# 2022.net
KiCad netlist of a schematic drawn in EAGLE
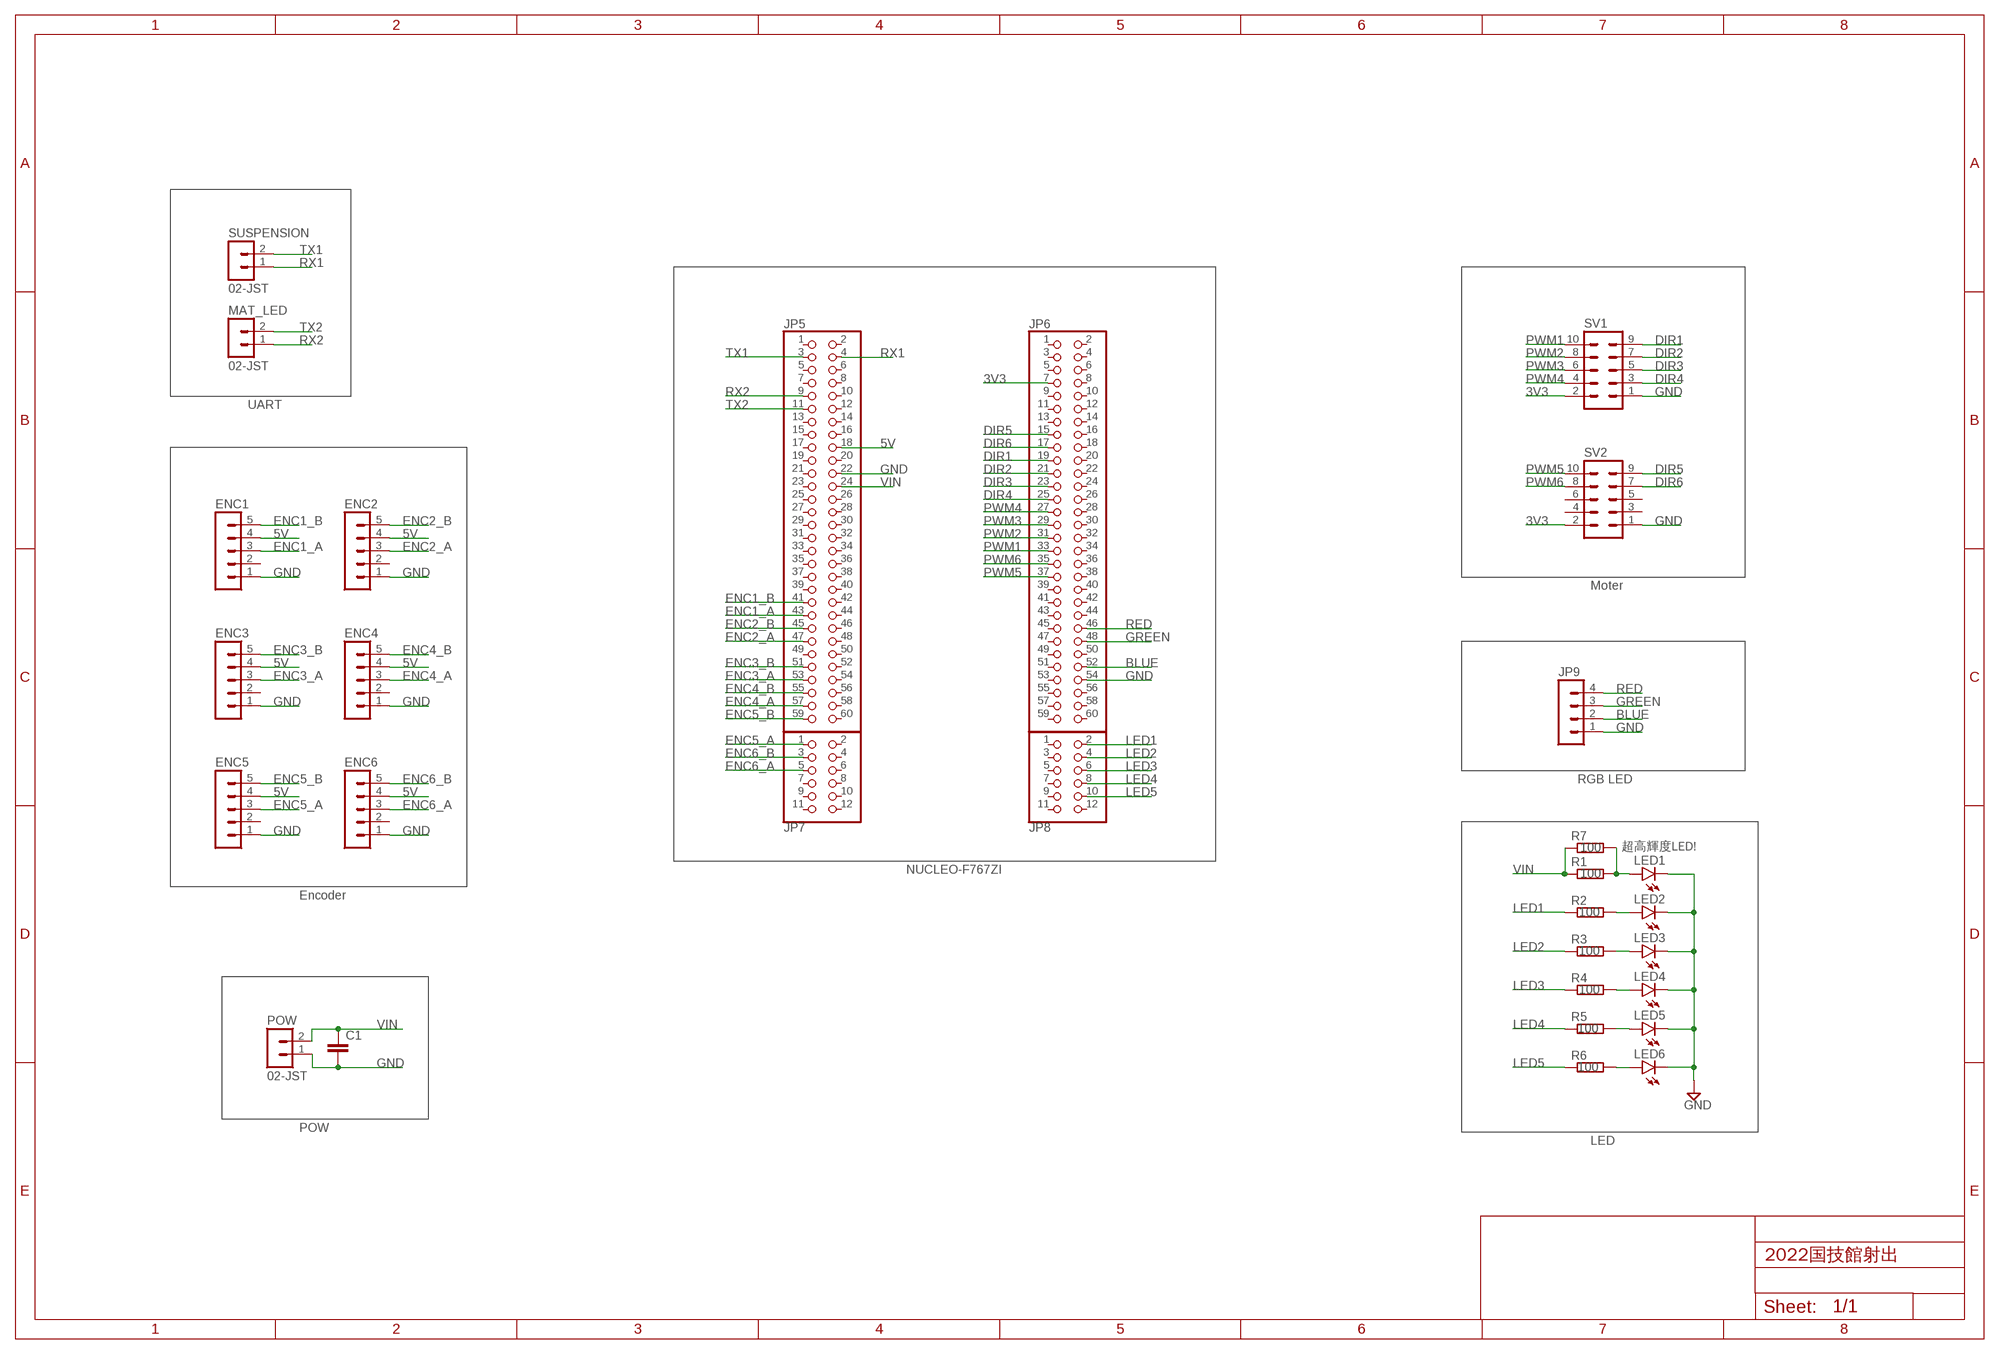
[diagram p0: schematic, sheet 1]

(export (version "E")
  (design (tool "Eeschema 10.0.6"))
  (components
    (comp (ref "C1")
      (value "C-EU025-024X044")
      (footprint "eagle-import:C025-024X044")
      (libsource (lib "eagle-import") (part "C-EU025-024X044"))
    )
    (comp (ref "ENC1")
      (value "05-JST")
      (footprint "eagle-import:B5B-XH")
      (libsource (lib "eagle-import") (part "05-JST"))
    )
    (comp (ref "ENC2")
      (value "05-JST")
      (footprint "eagle-import:B5B-XH")
      (libsource (lib "eagle-import") (part "05-JST"))
    )
    (comp (ref "ENC3")
      (value "05-JST")
      (footprint "eagle-import:B5B-XH")
      (libsource (lib "eagle-import") (part "05-JST"))
    )
    (comp (ref "ENC4")
      (value "05-JST")
      (footprint "eagle-import:B5B-XH")
      (libsource (lib "eagle-import") (part "05-JST"))
    )
    (comp (ref "ENC5")
      (value "05-JST")
      (footprint "eagle-import:B5B-XH")
      (libsource (lib "eagle-import") (part "05-JST"))
    )
    (comp (ref "ENC6")
      (value "05-JST")
      (footprint "eagle-import:B5B-XH")
      (libsource (lib "eagle-import") (part "05-JST"))
    )
    (comp (ref "JP5")
      (value "PINHD-2X30")
      (footprint "eagle-import:2X30")
      (libsource (lib "eagle-import") (part "PINHD-2X30"))
    )
    (comp (ref "JP6")
      (value "PINHD-2X30")
      (footprint "eagle-import:2X30")
      (libsource (lib "eagle-import") (part "PINHD-2X30"))
    )
    (comp (ref "JP7")
      (value "PINHD-2X6")
      (footprint "eagle-import:2X06")
      (libsource (lib "eagle-import") (part "PINHD-2X6"))
    )
    (comp (ref "JP8")
      (value "PINHD-2X6")
      (footprint "eagle-import:2X06")
      (libsource (lib "eagle-import") (part "PINHD-2X6"))
    )
    (comp (ref "JP9")
      (value "04-JST")
      (footprint "eagle-import:B4B-XH")
      (libsource (lib "eagle-import") (part "04-JST"))
    )
    (comp (ref "LED1")
      (value "LED5MM")
      (footprint "eagle-import:LED5MM")
      (libsource (lib "eagle-import") (part "LED5MM"))
    )
    (comp (ref "LED2")
      (value "LED5MM")
      (footprint "eagle-import:LED5MM")
      (libsource (lib "eagle-import") (part "LED5MM"))
    )
    (comp (ref "LED3")
      (value "LED5MM")
      (footprint "eagle-import:LED5MM")
      (libsource (lib "eagle-import") (part "LED5MM"))
    )
    (comp (ref "LED4")
      (value "LED5MM")
      (footprint "eagle-import:LED5MM")
      (libsource (lib "eagle-import") (part "LED5MM"))
    )
    (comp (ref "LED5")
      (value "LED5MM")
      (footprint "eagle-import:LED5MM")
      (libsource (lib "eagle-import") (part "LED5MM"))
    )
    (comp (ref "LED6")
      (value "LED5MM")
      (footprint "eagle-import:LED5MM")
      (libsource (lib "eagle-import") (part "LED5MM"))
    )
    (comp (ref "MAT_LED")
      (value "02-JST")
      (footprint "eagle-import:B2B-XH")
      (libsource (lib "eagle-import") (part "02-JST"))
    )
    (comp (ref "POW")
      (value "02-JST")
      (footprint "eagle-import:B2B-XH")
      (libsource (lib "eagle-import") (part "02-JST"))
    )
    (comp (ref "R1")
      (value "100")
      (footprint "eagle-import:0204_7")
      (libsource (lib "eagle-import") (part "R-EU_0204/7"))
    )
    (comp (ref "R2")
      (value "100")
      (footprint "eagle-import:0204_7")
      (libsource (lib "eagle-import") (part "R-EU_0204/7"))
    )
    (comp (ref "R3")
      (value "100")
      (footprint "eagle-import:0204_7")
      (libsource (lib "eagle-import") (part "R-EU_0204/7"))
    )
    (comp (ref "R4")
      (value "100")
      (footprint "eagle-import:0204_7")
      (libsource (lib "eagle-import") (part "R-EU_0204/7"))
    )
    (comp (ref "R5")
      (value "100")
      (footprint "eagle-import:0204_7")
      (libsource (lib "eagle-import") (part "R-EU_0204/7"))
    )
    (comp (ref "R6")
      (value "100")
      (footprint "eagle-import:0204_7")
      (libsource (lib "eagle-import") (part "R-EU_0204/7"))
    )
    (comp (ref "R7")
      (value "100")
      (footprint "eagle-import:0204_7")
      (libsource (lib "eagle-import") (part "R-EU_0204/7"))
    )
    (comp (ref "SUSPENSION")
      (value "02-JST")
      (footprint "eagle-import:B2B-XH")
      (libsource (lib "eagle-import") (part "02-JST"))
    )
    (comp (ref "SV1")
      (value "ML10")
      (footprint "eagle-import:ML10")
      (libsource (lib "eagle-import") (part "ML10"))
    )
    (comp (ref "SV2")
      (value "ML10")
      (footprint "eagle-import:ML10")
      (libsource (lib "eagle-import") (part "ML10"))
    )
  )
  (nets
    (net (code "1") (name "/3V3") (class "Default")
      (node (ref "JP6") (pin "7") (pinfunction "7_7") (pintype "passive"))
      (node (ref "SV1") (pin "2") (pinfunction "2_2") (pintype "passive"))
      (node (ref "SV2") (pin "2") (pinfunction "2_2") (pintype "passive"))
    )
    (net (code "2") (name "/5V") (class "Default")
      (node (ref "ENC1") (pin "4") (pinfunction "4_4") (pintype "passive"))
      (node (ref "ENC2") (pin "4") (pinfunction "4_4") (pintype "passive"))
      (node (ref "ENC3") (pin "4") (pinfunction "4_4") (pintype "passive"))
      (node (ref "ENC4") (pin "4") (pinfunction "4_4") (pintype "passive"))
      (node (ref "ENC5") (pin "4") (pinfunction "4_4") (pintype "passive"))
      (node (ref "ENC6") (pin "4") (pinfunction "4_4") (pintype "passive"))
      (node (ref "JP5") (pin "18") (pinfunction "18_18") (pintype "passive"))
    )
    (net (code "3") (name "/BLUE") (class "Default")
      (node (ref "JP6") (pin "52") (pinfunction "52_52") (pintype "passive"))
      (node (ref "JP9") (pin "2") (pinfunction "2_2") (pintype "passive"))
    )
    (net (code "4") (name "/DIR1") (class "Default")
      (node (ref "JP6") (pin "19") (pinfunction "19_19") (pintype "passive"))
      (node (ref "SV1") (pin "9") (pinfunction "9_9") (pintype "passive"))
    )
    (net (code "5") (name "/DIR2") (class "Default")
      (node (ref "JP6") (pin "21") (pinfunction "21_21") (pintype "passive"))
      (node (ref "SV1") (pin "7") (pinfunction "7_7") (pintype "passive"))
    )
    (net (code "6") (name "/DIR3") (class "Default")
      (node (ref "JP6") (pin "23") (pinfunction "23_23") (pintype "passive"))
      (node (ref "SV1") (pin "5") (pinfunction "5_5") (pintype "passive"))
    )
    (net (code "7") (name "/DIR4") (class "Default")
      (node (ref "JP6") (pin "25") (pinfunction "25_25") (pintype "passive"))
      (node (ref "SV1") (pin "3") (pinfunction "3_3") (pintype "passive"))
    )
    (net (code "8") (name "/DIR5") (class "Default")
      (node (ref "JP6") (pin "15") (pinfunction "15_15") (pintype "passive"))
      (node (ref "SV2") (pin "9") (pinfunction "9_9") (pintype "passive"))
    )
    (net (code "9") (name "/DIR6") (class "Default")
      (node (ref "JP6") (pin "17") (pinfunction "17_17") (pintype "passive"))
      (node (ref "SV2") (pin "7") (pinfunction "7_7") (pintype "passive"))
    )
    (net (code "10") (name "/ENC1_A") (class "Default")
      (node (ref "ENC1") (pin "3") (pinfunction "3_3") (pintype "passive"))
      (node (ref "JP5") (pin "43") (pinfunction "43_43") (pintype "passive"))
    )
    (net (code "11") (name "/ENC1_B") (class "Default")
      (node (ref "ENC1") (pin "5") (pinfunction "5_5") (pintype "passive"))
      (node (ref "JP5") (pin "41") (pinfunction "41_41") (pintype "passive"))
    )
    (net (code "12") (name "/ENC2_A") (class "Default")
      (node (ref "ENC2") (pin "3") (pinfunction "3_3") (pintype "passive"))
      (node (ref "JP5") (pin "47") (pinfunction "47_47") (pintype "passive"))
    )
    (net (code "13") (name "/ENC2_B") (class "Default")
      (node (ref "ENC2") (pin "5") (pinfunction "5_5") (pintype "passive"))
      (node (ref "JP5") (pin "45") (pinfunction "45_45") (pintype "passive"))
    )
    (net (code "14") (name "/ENC3_A") (class "Default")
      (node (ref "ENC3") (pin "3") (pinfunction "3_3") (pintype "passive"))
      (node (ref "JP5") (pin "53") (pinfunction "53_53") (pintype "passive"))
    )
    (net (code "15") (name "/ENC3_B") (class "Default")
      (node (ref "ENC3") (pin "5") (pinfunction "5_5") (pintype "passive"))
      (node (ref "JP5") (pin "51") (pinfunction "51_51") (pintype "passive"))
    )
    (net (code "16") (name "/ENC4_A") (class "Default")
      (node (ref "ENC4") (pin "3") (pinfunction "3_3") (pintype "passive"))
      (node (ref "JP5") (pin "57") (pinfunction "57_57") (pintype "passive"))
    )
    (net (code "17") (name "/ENC4_B") (class "Default")
      (node (ref "ENC4") (pin "5") (pinfunction "5_5") (pintype "passive"))
      (node (ref "JP5") (pin "55") (pinfunction "55_55") (pintype "passive"))
    )
    (net (code "18") (name "/ENC5_A") (class "Default")
      (node (ref "ENC5") (pin "3") (pinfunction "3_3") (pintype "passive"))
      (node (ref "JP7") (pin "1") (pinfunction "1_1") (pintype "passive"))
    )
    (net (code "19") (name "/ENC5_B") (class "Default")
      (node (ref "ENC5") (pin "5") (pinfunction "5_5") (pintype "passive"))
      (node (ref "JP5") (pin "59") (pinfunction "59_59") (pintype "passive"))
    )
    (net (code "20") (name "/ENC6_A") (class "Default")
      (node (ref "ENC6") (pin "3") (pinfunction "3_3") (pintype "passive"))
      (node (ref "JP7") (pin "5") (pinfunction "5_5") (pintype "passive"))
    )
    (net (code "21") (name "/ENC6_B") (class "Default")
      (node (ref "ENC6") (pin "5") (pinfunction "5_5") (pintype "passive"))
      (node (ref "JP7") (pin "3") (pinfunction "3_3") (pintype "passive"))
    )
    (net (code "22") (name "/GREEN") (class "Default")
      (node (ref "JP6") (pin "48") (pinfunction "48_48") (pintype "passive"))
      (node (ref "JP9") (pin "3") (pinfunction "3_3") (pintype "passive"))
    )
    (net (code "23") (name "/LED1") (class "Default")
      (node (ref "JP8") (pin "2") (pinfunction "2_2") (pintype "passive"))
      (node (ref "R2") (pin "1") (pinfunction "1_1") (pintype "passive"))
    )
    (net (code "24") (name "/LED2") (class "Default")
      (node (ref "JP8") (pin "4") (pinfunction "4_4") (pintype "passive"))
      (node (ref "R3") (pin "1") (pinfunction "1_1") (pintype "passive"))
    )
    (net (code "25") (name "/LED3") (class "Default")
      (node (ref "JP8") (pin "6") (pinfunction "6_6") (pintype "passive"))
      (node (ref "R4") (pin "1") (pinfunction "1_1") (pintype "passive"))
    )
    (net (code "26") (name "/LED4") (class "Default")
      (node (ref "JP8") (pin "8") (pinfunction "8_8") (pintype "passive"))
      (node (ref "R5") (pin "1") (pinfunction "1_1") (pintype "passive"))
    )
    (net (code "27") (name "/LED5") (class "Default")
      (node (ref "JP8") (pin "10") (pinfunction "10_10") (pintype "passive"))
      (node (ref "R6") (pin "1") (pinfunction "1_1") (pintype "passive"))
    )
    (net (code "28") (name "/PWM1") (class "Default")
      (node (ref "JP6") (pin "33") (pinfunction "33_33") (pintype "passive"))
      (node (ref "SV1") (pin "10") (pinfunction "10_10") (pintype "passive"))
    )
    (net (code "29") (name "/PWM2") (class "Default")
      (node (ref "JP6") (pin "31") (pinfunction "31_31") (pintype "passive"))
      (node (ref "SV1") (pin "8") (pinfunction "8_8") (pintype "passive"))
    )
    (net (code "30") (name "/PWM3") (class "Default")
      (node (ref "JP6") (pin "29") (pinfunction "29_29") (pintype "passive"))
      (node (ref "SV1") (pin "6") (pinfunction "6_6") (pintype "passive"))
    )
    (net (code "31") (name "/PWM4") (class "Default")
      (node (ref "JP6") (pin "27") (pinfunction "27_27") (pintype "passive"))
      (node (ref "SV1") (pin "4") (pinfunction "4_4") (pintype "passive"))
    )
    (net (code "32") (name "/PWM5") (class "Default")
      (node (ref "JP6") (pin "37") (pinfunction "37_37") (pintype "passive"))
      (node (ref "SV2") (pin "10") (pinfunction "10_10") (pintype "passive"))
    )
    (net (code "33") (name "/PWM6") (class "Default")
      (node (ref "JP6") (pin "35") (pinfunction "35_35") (pintype "passive"))
      (node (ref "SV2") (pin "8") (pinfunction "8_8") (pintype "passive"))
    )
    (net (code "34") (name "/RED") (class "Default")
      (node (ref "JP6") (pin "46") (pinfunction "46_46") (pintype "passive"))
      (node (ref "JP9") (pin "4") (pinfunction "4_4") (pintype "passive"))
    )
    (net (code "35") (name "/RX1") (class "Default")
      (node (ref "JP5") (pin "4") (pinfunction "4_4") (pintype "passive"))
      (node (ref "SUSPENSION") (pin "1") (pinfunction "1_1") (pintype "passive"))
    )
    (net (code "36") (name "/RX2") (class "Default")
      (node (ref "JP5") (pin "9") (pinfunction "9_9") (pintype "passive"))
      (node (ref "MAT_LED") (pin "1") (pinfunction "1_1") (pintype "passive"))
    )
    (net (code "37") (name "/TX1") (class "Default")
      (node (ref "JP5") (pin "3") (pinfunction "3_3") (pintype "passive"))
      (node (ref "SUSPENSION") (pin "2") (pinfunction "2_2") (pintype "passive"))
    )
    (net (code "38") (name "/TX2") (class "Default")
      (node (ref "JP5") (pin "11") (pinfunction "11_11") (pintype "passive"))
      (node (ref "MAT_LED") (pin "2") (pinfunction "2_2") (pintype "passive"))
    )
    (net (code "39") (name "/VIN") (class "Default")
      (node (ref "C1") (pin "1") (pinfunction "1_1") (pintype "passive"))
      (node (ref "JP5") (pin "24") (pinfunction "24_24") (pintype "passive"))
      (node (ref "POW") (pin "2") (pinfunction "2_2") (pintype "passive"))
      (node (ref "R1") (pin "1") (pinfunction "1_1") (pintype "passive"))
      (node (ref "R7") (pin "1") (pinfunction "1_1") (pintype "passive"))
    )
    (net (code "40") (name "GND") (class "Default")
      (node (ref "C1") (pin "2") (pinfunction "2_2") (pintype "passive"))
      (node (ref "ENC1") (pin "1") (pinfunction "1_1") (pintype "passive"))
      (node (ref "ENC2") (pin "1") (pinfunction "1_1") (pintype "passive"))
      (node (ref "ENC3") (pin "1") (pinfunction "1_1") (pintype "passive"))
      (node (ref "ENC4") (pin "1") (pinfunction "1_1") (pintype "passive"))
      (node (ref "ENC5") (pin "1") (pinfunction "1_1") (pintype "passive"))
      (node (ref "ENC6") (pin "1") (pinfunction "1_1") (pintype "passive"))
      (node (ref "JP5") (pin "22") (pinfunction "22_22") (pintype "passive"))
      (node (ref "JP6") (pin "54") (pinfunction "54_54") (pintype "passive"))
      (node (ref "JP9") (pin "1") (pinfunction "1_1") (pintype "passive"))
      (node (ref "LED1") (pin "K") (pinfunction "C_K") (pintype "passive"))
      (node (ref "LED2") (pin "K") (pinfunction "C_K") (pintype "passive"))
      (node (ref "LED3") (pin "K") (pinfunction "C_K") (pintype "passive"))
      (node (ref "LED4") (pin "K") (pinfunction "C_K") (pintype "passive"))
      (node (ref "LED5") (pin "K") (pinfunction "C_K") (pintype "passive"))
      (node (ref "LED6") (pin "K") (pinfunction "C_K") (pintype "passive"))
      (node (ref "POW") (pin "1") (pinfunction "1_1") (pintype "passive"))
      (node (ref "SV1") (pin "1") (pinfunction "1_1") (pintype "passive"))
      (node (ref "SV2") (pin "1") (pinfunction "1_1") (pintype "passive"))
    )
    (net (code "41") (name "Net-(LED1-PadA)") (class "Default")
      (node (ref "LED1") (pin "A") (pinfunction "A_A") (pintype "passive"))
      (node (ref "R1") (pin "2") (pinfunction "2_2") (pintype "passive"))
      (node (ref "R7") (pin "2") (pinfunction "2_2") (pintype "passive"))
    )
    (net (code "42") (name "Net-(LED2-PadA)") (class "Default")
      (node (ref "LED2") (pin "A") (pinfunction "A_A") (pintype "passive"))
      (node (ref "R2") (pin "2") (pinfunction "2_2") (pintype "passive"))
    )
    (net (code "43") (name "Net-(LED3-PadA)") (class "Default")
      (node (ref "LED3") (pin "A") (pinfunction "A_A") (pintype "passive"))
      (node (ref "R3") (pin "2") (pinfunction "2_2") (pintype "passive"))
    )
    (net (code "44") (name "Net-(LED4-PadA)") (class "Default")
      (node (ref "LED4") (pin "A") (pinfunction "A_A") (pintype "passive"))
      (node (ref "R4") (pin "2") (pinfunction "2_2") (pintype "passive"))
    )
    (net (code "45") (name "Net-(LED5-PadA)") (class "Default")
      (node (ref "LED5") (pin "A") (pinfunction "A_A") (pintype "passive"))
      (node (ref "R5") (pin "2") (pinfunction "2_2") (pintype "passive"))
    )
    (net (code "46") (name "Net-(LED6-PadA)") (class "Default")
      (node (ref "LED6") (pin "A") (pinfunction "A_A") (pintype "passive"))
      (node (ref "R6") (pin "2") (pinfunction "2_2") (pintype "passive"))
    )
    (net (code "47") (name "unconnected-(ENC1-Pad2)") (class "Default")
      (node (ref "ENC1") (pin "2") (pinfunction "2_2") (pintype "passive"))
    )
    (net (code "48") (name "unconnected-(ENC2-Pad2)") (class "Default")
      (node (ref "ENC2") (pin "2") (pinfunction "2_2") (pintype "passive"))
    )
    (net (code "49") (name "unconnected-(ENC3-Pad2)") (class "Default")
      (node (ref "ENC3") (pin "2") (pinfunction "2_2") (pintype "passive"))
    )
    (net (code "50") (name "unconnected-(ENC4-Pad2)") (class "Default")
      (node (ref "ENC4") (pin "2") (pinfunction "2_2") (pintype "passive"))
    )
    (net (code "51") (name "unconnected-(ENC5-Pad2)") (class "Default")
      (node (ref "ENC5") (pin "2") (pinfunction "2_2") (pintype "passive"))
    )
    (net (code "52") (name "unconnected-(ENC6-Pad2)") (class "Default")
      (node (ref "ENC6") (pin "2") (pinfunction "2_2") (pintype "passive"))
    )
    (net (code "53") (name "unconnected-(JP5-Pad1)") (class "Default")
      (node (ref "JP5") (pin "1") (pinfunction "1_1") (pintype "passive"))
    )
    (net (code "54") (name "unconnected-(JP5-Pad2)") (class "Default")
      (node (ref "JP5") (pin "2") (pinfunction "2_2") (pintype "passive"))
    )
    (net (code "55") (name "unconnected-(JP5-Pad5)") (class "Default")
      (node (ref "JP5") (pin "5") (pinfunction "5_5") (pintype "passive"))
    )
    (net (code "56") (name "unconnected-(JP5-Pad6)") (class "Default")
      (node (ref "JP5") (pin "6") (pinfunction "6_6") (pintype "passive"))
    )
    (net (code "57") (name "unconnected-(JP5-Pad7)") (class "Default")
      (node (ref "JP5") (pin "7") (pinfunction "7_7") (pintype "passive"))
    )
    (net (code "58") (name "unconnected-(JP5-Pad8)") (class "Default")
      (node (ref "JP5") (pin "8") (pinfunction "8_8") (pintype "passive"))
    )
    (net (code "59") (name "unconnected-(JP5-Pad10)") (class "Default")
      (node (ref "JP5") (pin "10") (pinfunction "10_10") (pintype "passive"))
    )
    (net (code "60") (name "unconnected-(JP5-Pad12)") (class "Default")
      (node (ref "JP5") (pin "12") (pinfunction "12_12") (pintype "passive"))
    )
    (net (code "61") (name "unconnected-(JP5-Pad13)") (class "Default")
      (node (ref "JP5") (pin "13") (pinfunction "13_13") (pintype "passive"))
    )
    (net (code "62") (name "unconnected-(JP5-Pad14)") (class "Default")
      (node (ref "JP5") (pin "14") (pinfunction "14_14") (pintype "passive"))
    )
    (net (code "63") (name "unconnected-(JP5-Pad15)") (class "Default")
      (node (ref "JP5") (pin "15") (pinfunction "15_15") (pintype "passive"))
    )
    (net (code "64") (name "unconnected-(JP5-Pad16)") (class "Default")
      (node (ref "JP5") (pin "16") (pinfunction "16_16") (pintype "passive"))
    )
    (net (code "65") (name "unconnected-(JP5-Pad17)") (class "Default")
      (node (ref "JP5") (pin "17") (pinfunction "17_17") (pintype "passive"))
    )
    (net (code "66") (name "unconnected-(JP5-Pad19)") (class "Default")
      (node (ref "JP5") (pin "19") (pinfunction "19_19") (pintype "passive"))
    )
    (net (code "67") (name "unconnected-(JP5-Pad20)") (class "Default")
      (node (ref "JP5") (pin "20") (pinfunction "20_20") (pintype "passive"))
    )
    (net (code "68") (name "unconnected-(JP5-Pad21)") (class "Default")
      (node (ref "JP5") (pin "21") (pinfunction "21_21") (pintype "passive"))
    )
    (net (code "69") (name "unconnected-(JP5-Pad23)") (class "Default")
      (node (ref "JP5") (pin "23") (pinfunction "23_23") (pintype "passive"))
    )
    (net (code "70") (name "unconnected-(JP5-Pad25)") (class "Default")
      (node (ref "JP5") (pin "25") (pinfunction "25_25") (pintype "passive"))
    )
    (net (code "71") (name "unconnected-(JP5-Pad26)") (class "Default")
      (node (ref "JP5") (pin "26") (pinfunction "26_26") (pintype "passive"))
    )
    (net (code "72") (name "unconnected-(JP5-Pad27)") (class "Default")
      (node (ref "JP5") (pin "27") (pinfunction "27_27") (pintype "passive"))
    )
    (net (code "73") (name "unconnected-(JP5-Pad28)") (class "Default")
      (node (ref "JP5") (pin "28") (pinfunction "28_28") (pintype "passive"))
    )
    (net (code "74") (name "unconnected-(JP5-Pad29)") (class "Default")
      (node (ref "JP5") (pin "29") (pinfunction "29_29") (pintype "passive"))
    )
    (net (code "75") (name "unconnected-(JP5-Pad30)") (class "Default")
      (node (ref "JP5") (pin "30") (pinfunction "30_30") (pintype "passive"))
    )
    (net (code "76") (name "unconnected-(JP5-Pad31)") (class "Default")
      (node (ref "JP5") (pin "31") (pinfunction "31_31") (pintype "passive"))
    )
    (net (code "77") (name "unconnected-(JP5-Pad32)") (class "Default")
      (node (ref "JP5") (pin "32") (pinfunction "32_32") (pintype "passive"))
    )
    (net (code "78") (name "unconnected-(JP5-Pad33)") (class "Default")
      (node (ref "JP5") (pin "33") (pinfunction "33_33") (pintype "passive"))
    )
    (net (code "79") (name "unconnected-(JP5-Pad34)") (class "Default")
      (node (ref "JP5") (pin "34") (pinfunction "34_34") (pintype "passive"))
    )
    (net (code "80") (name "unconnected-(JP5-Pad35)") (class "Default")
      (node (ref "JP5") (pin "35") (pinfunction "35_35") (pintype "passive"))
    )
    (net (code "81") (name "unconnected-(JP5-Pad36)") (class "Default")
      (node (ref "JP5") (pin "36") (pinfunction "36_36") (pintype "passive"))
    )
    (net (code "82") (name "unconnected-(JP5-Pad37)") (class "Default")
      (node (ref "JP5") (pin "37") (pinfunction "37_37") (pintype "passive"))
    )
    (net (code "83") (name "unconnected-(JP5-Pad38)") (class "Default")
      (node (ref "JP5") (pin "38") (pinfunction "38_38") (pintype "passive"))
    )
    (net (code "84") (name "unconnected-(JP5-Pad39)") (class "Default")
      (node (ref "JP5") (pin "39") (pinfunction "39_39") (pintype "passive"))
    )
    (net (code "85") (name "unconnected-(JP5-Pad40)") (class "Default")
      (node (ref "JP5") (pin "40") (pinfunction "40_40") (pintype "passive"))
    )
    (net (code "86") (name "unconnected-(JP5-Pad42)") (class "Default")
      (node (ref "JP5") (pin "42") (pinfunction "42_42") (pintype "passive"))
    )
    (net (code "87") (name "unconnected-(JP5-Pad44)") (class "Default")
      (node (ref "JP5") (pin "44") (pinfunction "44_44") (pintype "passive"))
    )
    (net (code "88") (name "unconnected-(JP5-Pad46)") (class "Default")
      (node (ref "JP5") (pin "46") (pinfunction "46_46") (pintype "passive"))
    )
    (net (code "89") (name "unconnected-(JP5-Pad48)") (class "Default")
      (node (ref "JP5") (pin "48") (pinfunction "48_48") (pintype "passive"))
    )
    (net (code "90") (name "unconnected-(JP5-Pad49)") (class "Default")
      (node (ref "JP5") (pin "49") (pinfunction "49_49") (pintype "passive"))
    )
    (net (code "91") (name "unconnected-(JP5-Pad50)") (class "Default")
      (node (ref "JP5") (pin "50") (pinfunction "50_50") (pintype "passive"))
    )
    (net (code "92") (name "unconnected-(JP5-Pad52)") (class "Default")
      (node (ref "JP5") (pin "52") (pinfunction "52_52") (pintype "passive"))
    )
    (net (code "93") (name "unconnected-(JP5-Pad54)") (class "Default")
      (node (ref "JP5") (pin "54") (pinfunction "54_54") (pintype "passive"))
    )
    (net (code "94") (name "unconnected-(JP5-Pad56)") (class "Default")
      (node (ref "JP5") (pin "56") (pinfunction "56_56") (pintype "passive"))
    )
    (net (code "95") (name "unconnected-(JP5-Pad58)") (class "Default")
      (node (ref "JP5") (pin "58") (pinfunction "58_58") (pintype "passive"))
    )
    (net (code "96") (name "unconnected-(JP5-Pad60)") (class "Default")
      (node (ref "JP5") (pin "60") (pinfunction "60_60") (pintype "passive"))
    )
    (net (code "97") (name "unconnected-(JP6-Pad1)") (class "Default")
      (node (ref "JP6") (pin "1") (pinfunction "1_1") (pintype "passive"))
    )
    (net (code "98") (name "unconnected-(JP6-Pad2)") (class "Default")
      (node (ref "JP6") (pin "2") (pinfunction "2_2") (pintype "passive"))
    )
    (net (code "99") (name "unconnected-(JP6-Pad3)") (class "Default")
      (node (ref "JP6") (pin "3") (pinfunction "3_3") (pintype "passive"))
    )
    (net (code "100") (name "unconnected-(JP6-Pad4)") (class "Default")
      (node (ref "JP6") (pin "4") (pinfunction "4_4") (pintype "passive"))
    )
    (net (code "101") (name "unconnected-(JP6-Pad5)") (class "Default")
      (node (ref "JP6") (pin "5") (pinfunction "5_5") (pintype "passive"))
    )
    (net (code "102") (name "unconnected-(JP6-Pad6)") (class "Default")
      (node (ref "JP6") (pin "6") (pinfunction "6_6") (pintype "passive"))
    )
    (net (code "103") (name "unconnected-(JP6-Pad8)") (class "Default")
      (node (ref "JP6") (pin "8") (pinfunction "8_8") (pintype "passive"))
    )
    (net (code "104") (name "unconnected-(JP6-Pad9)") (class "Default")
      (node (ref "JP6") (pin "9") (pinfunction "9_9") (pintype "passive"))
    )
    (net (code "105") (name "unconnected-(JP6-Pad10)") (class "Default")
      (node (ref "JP6") (pin "10") (pinfunction "10_10") (pintype "passive"))
    )
    (net (code "106") (name "unconnected-(JP6-Pad11)") (class "Default")
      (node (ref "JP6") (pin "11") (pinfunction "11_11") (pintype "passive"))
    )
    (net (code "107") (name "unconnected-(JP6-Pad12)") (class "Default")
      (node (ref "JP6") (pin "12") (pinfunction "12_12") (pintype "passive"))
    )
    (net (code "108") (name "unconnected-(JP6-Pad13)") (class "Default")
      (node (ref "JP6") (pin "13") (pinfunction "13_13") (pintype "passive"))
    )
    (net (code "109") (name "unconnected-(JP6-Pad14)") (class "Default")
      (node (ref "JP6") (pin "14") (pinfunction "14_14") (pintype "passive"))
    )
    (net (code "110") (name "unconnected-(JP6-Pad16)") (class "Default")
      (node (ref "JP6") (pin "16") (pinfunction "16_16") (pintype "passive"))
    )
    (net (code "111") (name "unconnected-(JP6-Pad18)") (class "Default")
      (node (ref "JP6") (pin "18") (pinfunction "18_18") (pintype "passive"))
    )
    (net (code "112") (name "unconnected-(JP6-Pad20)") (class "Default")
      (node (ref "JP6") (pin "20") (pinfunction "20_20") (pintype "passive"))
    )
    (net (code "113") (name "unconnected-(JP6-Pad22)") (class "Default")
      (node (ref "JP6") (pin "22") (pinfunction "22_22") (pintype "passive"))
    )
    (net (code "114") (name "unconnected-(JP6-Pad24)") (class "Default")
      (node (ref "JP6") (pin "24") (pinfunction "24_24") (pintype "passive"))
    )
    (net (code "115") (name "unconnected-(JP6-Pad26)") (class "Default")
      (node (ref "JP6") (pin "26") (pinfunction "26_26") (pintype "passive"))
    )
    (net (code "116") (name "unconnected-(JP6-Pad28)") (class "Default")
      (node (ref "JP6") (pin "28") (pinfunction "28_28") (pintype "passive"))
    )
    (net (code "117") (name "unconnected-(JP6-Pad30)") (class "Default")
      (node (ref "JP6") (pin "30") (pinfunction "30_30") (pintype "passive"))
    )
    (net (code "118") (name "unconnected-(JP6-Pad32)") (class "Default")
      (node (ref "JP6") (pin "32") (pinfunction "32_32") (pintype "passive"))
    )
    (net (code "119") (name "unconnected-(JP6-Pad34)") (class "Default")
      (node (ref "JP6") (pin "34") (pinfunction "34_34") (pintype "passive"))
    )
    (net (code "120") (name "unconnected-(JP6-Pad36)") (class "Default")
      (node (ref "JP6") (pin "36") (pinfunction "36_36") (pintype "passive"))
    )
    (net (code "121") (name "unconnected-(JP6-Pad38)") (class "Default")
      (node (ref "JP6") (pin "38") (pinfunction "38_38") (pintype "passive"))
    )
    (net (code "122") (name "unconnected-(JP6-Pad39)") (class "Default")
      (node (ref "JP6") (pin "39") (pinfunction "39_39") (pintype "passive"))
    )
    (net (code "123") (name "unconnected-(JP6-Pad40)") (class "Default")
      (node (ref "JP6") (pin "40") (pinfunction "40_40") (pintype "passive"))
    )
    (net (code "124") (name "unconnected-(JP6-Pad41)") (class "Default")
      (node (ref "JP6") (pin "41") (pinfunction "41_41") (pintype "passive"))
    )
    (net (code "125") (name "unconnected-(JP6-Pad42)") (class "Default")
      (node (ref "JP6") (pin "42") (pinfunction "42_42") (pintype "passive"))
    )
    (net (code "126") (name "unconnected-(JP6-Pad43)") (class "Default")
      (node (ref "JP6") (pin "43") (pinfunction "43_43") (pintype "passive"))
    )
    (net (code "127") (name "unconnected-(JP6-Pad44)") (class "Default")
      (node (ref "JP6") (pin "44") (pinfunction "44_44") (pintype "passive"))
    )
    (net (code "128") (name "unconnected-(JP6-Pad45)") (class "Default")
      (node (ref "JP6") (pin "45") (pinfunction "45_45") (pintype "passive"))
    )
    (net (code "129") (name "unconnected-(JP6-Pad47)") (class "Default")
      (node (ref "JP6") (pin "47") (pinfunction "47_47") (pintype "passive"))
    )
    (net (code "130") (name "unconnected-(JP6-Pad49)") (class "Default")
      (node (ref "JP6") (pin "49") (pinfunction "49_49") (pintype "passive"))
    )
    (net (code "131") (name "unconnected-(JP6-Pad50)") (class "Default")
      (node (ref "JP6") (pin "50") (pinfunction "50_50") (pintype "passive"))
    )
    (net (code "132") (name "unconnected-(JP6-Pad51)") (class "Default")
      (node (ref "JP6") (pin "51") (pinfunction "51_51") (pintype "passive"))
    )
    (net (code "133") (name "unconnected-(JP6-Pad53)") (class "Default")
      (node (ref "JP6") (pin "53") (pinfunction "53_53") (pintype "passive"))
    )
    (net (code "134") (name "unconnected-(JP6-Pad55)") (class "Default")
      (node (ref "JP6") (pin "55") (pinfunction "55_55") (pintype "passive"))
    )
    (net (code "135") (name "unconnected-(JP6-Pad56)") (class "Default")
      (node (ref "JP6") (pin "56") (pinfunction "56_56") (pintype "passive"))
    )
    (net (code "136") (name "unconnected-(JP6-Pad57)") (class "Default")
      (node (ref "JP6") (pin "57") (pinfunction "57_57") (pintype "passive"))
    )
    (net (code "137") (name "unconnected-(JP6-Pad58)") (class "Default")
      (node (ref "JP6") (pin "58") (pinfunction "58_58") (pintype "passive"))
    )
    (net (code "138") (name "unconnected-(JP6-Pad59)") (class "Default")
      (node (ref "JP6") (pin "59") (pinfunction "59_59") (pintype "passive"))
    )
    (net (code "139") (name "unconnected-(JP6-Pad60)") (class "Default")
      (node (ref "JP6") (pin "60") (pinfunction "60_60") (pintype "passive"))
    )
    (net (code "140") (name "unconnected-(JP7-Pad2)") (class "Default")
      (node (ref "JP7") (pin "2") (pinfunction "2_2") (pintype "passive"))
    )
    (net (code "141") (name "unconnected-(JP7-Pad4)") (class "Default")
      (node (ref "JP7") (pin "4") (pinfunction "4_4") (pintype "passive"))
    )
    (net (code "142") (name "unconnected-(JP7-Pad6)") (class "Default")
      (node (ref "JP7") (pin "6") (pinfunction "6_6") (pintype "passive"))
    )
    (net (code "143") (name "unconnected-(JP7-Pad7)") (class "Default")
      (node (ref "JP7") (pin "7") (pinfunction "7_7") (pintype "passive"))
    )
    (net (code "144") (name "unconnected-(JP7-Pad8)") (class "Default")
      (node (ref "JP7") (pin "8") (pinfunction "8_8") (pintype "passive"))
    )
    (net (code "145") (name "unconnected-(JP7-Pad9)") (class "Default")
      (node (ref "JP7") (pin "9") (pinfunction "9_9") (pintype "passive"))
    )
    (net (code "146") (name "unconnected-(JP7-Pad10)") (class "Default")
      (node (ref "JP7") (pin "10") (pinfunction "10_10") (pintype "passive"))
    )
    (net (code "147") (name "unconnected-(JP7-Pad11)") (class "Default")
      (node (ref "JP7") (pin "11") (pinfunction "11_11") (pintype "passive"))
    )
    (net (code "148") (name "unconnected-(JP7-Pad12)") (class "Default")
      (node (ref "JP7") (pin "12") (pinfunction "12_12") (pintype "passive"))
    )
    (net (code "149") (name "unconnected-(JP8-Pad1)") (class "Default")
      (node (ref "JP8") (pin "1") (pinfunction "1_1") (pintype "passive"))
    )
    (net (code "150") (name "unconnected-(JP8-Pad3)") (class "Default")
      (node (ref "JP8") (pin "3") (pinfunction "3_3") (pintype "passive"))
    )
    (net (code "151") (name "unconnected-(JP8-Pad5)") (class "Default")
      (node (ref "JP8") (pin "5") (pinfunction "5_5") (pintype "passive"))
    )
    (net (code "152") (name "unconnected-(JP8-Pad7)") (class "Default")
      (node (ref "JP8") (pin "7") (pinfunction "7_7") (pintype "passive"))
    )
    (net (code "153") (name "unconnected-(JP8-Pad9)") (class "Default")
      (node (ref "JP8") (pin "9") (pinfunction "9_9") (pintype "passive"))
    )
    (net (code "154") (name "unconnected-(JP8-Pad11)") (class "Default")
      (node (ref "JP8") (pin "11") (pinfunction "11_11") (pintype "passive"))
    )
    (net (code "155") (name "unconnected-(JP8-Pad12)") (class "Default")
      (node (ref "JP8") (pin "12") (pinfunction "12_12") (pintype "passive"))
    )
    (net (code "156") (name "unconnected-(SV2-Pad3)") (class "Default")
      (node (ref "SV2") (pin "3") (pinfunction "3_3") (pintype "passive"))
    )
    (net (code "157") (name "unconnected-(SV2-Pad4)") (class "Default")
      (node (ref "SV2") (pin "4") (pinfunction "4_4") (pintype "passive"))
    )
    (net (code "158") (name "unconnected-(SV2-Pad5)") (class "Default")
      (node (ref "SV2") (pin "5") (pinfunction "5_5") (pintype "passive"))
    )
    (net (code "159") (name "unconnected-(SV2-Pad6)") (class "Default")
      (node (ref "SV2") (pin "6") (pinfunction "6_6") (pintype "passive"))
    )
  )
)
